# TopLevel.net
KiCad netlist of a schematic drawn in Altium Designer
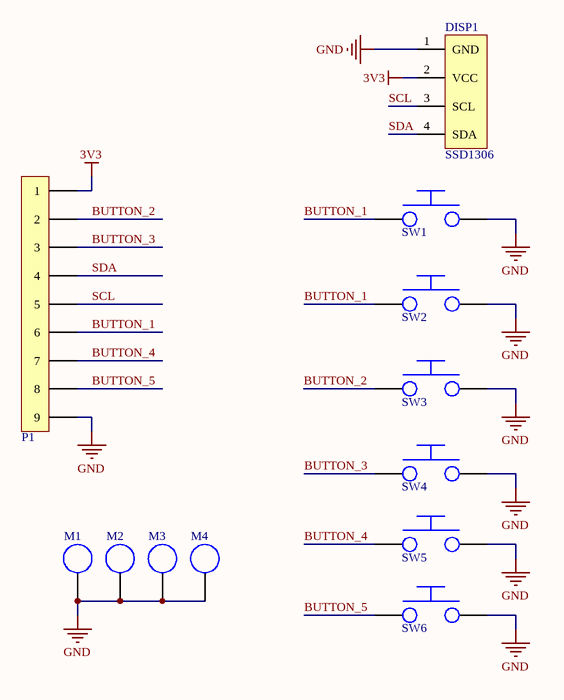
[diagram p0: TopLevel.SchDoc]

(export (version "E")
  (design (tool "Eeschema 10.0.6"))
  (components
    (comp (ref "DISP1")
      (value "SSD1306")
      (footprint "SSD1306_1.3")
      (description "SSD1306 128*64 1.3Inch I2C OLED Module")
      (libsource (lib "OneFader") (part "SSD1306_1.3"))
    )
    (comp (ref "M1")
      (value "M3 Flat Screw")
      (footprint "M3 Screw")
      (libsource (lib "OneFader") (part "M3 Flat Screw"))
    )
    (comp (ref "M2")
      (value "M3 Flat Screw")
      (footprint "M3 Screw")
      (libsource (lib "OneFader") (part "M3 Flat Screw"))
    )
    (comp (ref "M3")
      (value "M3 Flat Screw")
      (footprint "M3 Screw")
      (libsource (lib "OneFader") (part "M3 Flat Screw"))
    )
    (comp (ref "M4")
      (value "M3 Flat Screw")
      (footprint "M3 Screw")
      (libsource (lib "OneFader") (part "M3 Flat Screw"))
    )
    (comp (ref "P1") (value "9 Header") (footprint "9 Header") (libsource (lib "OneFader") (part "9 Header")))
    (comp (ref "SW1")
      (value "Momentary Button")
      (footprint "TD-19XA")
      (libsource (lib "OneFader") (part "Momentary Button"))
    )
    (comp (ref "SW2")
      (value "Momentary Button")
      (footprint "TS1127")
      (libsource (lib "OneFader") (part "Momentary Button"))
    )
    (comp (ref "SW3")
      (value "Momentary Button")
      (footprint "Tactile Button 6*6*5mm")
      (libsource (lib "OneFader") (part "Momentary Button"))
    )
    (comp (ref "SW4")
      (value "Momentary Button")
      (footprint "Tactile Button 6*6*5mm")
      (libsource (lib "OneFader") (part "Momentary Button"))
    )
    (comp (ref "SW5")
      (value "Momentary Button")
      (footprint "Tactile Button 6*6*5mm")
      (libsource (lib "OneFader") (part "Momentary Button"))
    )
    (comp (ref "SW6")
      (value "Momentary Button")
      (footprint "Tactile Button 6*6*5mm")
      (libsource (lib "OneFader") (part "Momentary Button"))
    )
  )
  (nets
    (net (code "1") (name "/BUTTON_1") (class "Default")
      (node (ref "P1") (pin "6") (pinfunction "6_6") (pintype "passive"))
      (node (ref "SW1") (pin "1") (pinfunction "1_1") (pintype "passive"))
      (node (ref "SW2") (pin "1") (pinfunction "1_1") (pintype "passive"))
    )
    (net (code "2") (name "/BUTTON_2") (class "Default")
      (node (ref "P1") (pin "2") (pinfunction "2_2") (pintype "passive"))
      (node (ref "SW3") (pin "1") (pinfunction "1_1") (pintype "passive"))
    )
    (net (code "3") (name "/BUTTON_3") (class "Default")
      (node (ref "P1") (pin "3") (pinfunction "3_3") (pintype "passive"))
      (node (ref "SW4") (pin "1") (pinfunction "1_1") (pintype "passive"))
    )
    (net (code "4") (name "/BUTTON_4") (class "Default")
      (node (ref "P1") (pin "7") (pinfunction "7_7") (pintype "passive"))
      (node (ref "SW5") (pin "1") (pinfunction "1_1") (pintype "passive"))
    )
    (net (code "5") (name "/BUTTON_5") (class "Default")
      (node (ref "P1") (pin "8") (pinfunction "8_8") (pintype "passive"))
      (node (ref "SW6") (pin "1") (pinfunction "1_1") (pintype "passive"))
    )
    (net (code "6") (name "/SCL") (class "Default")
      (node (ref "DISP1") (pin "3") (pinfunction "SCL_3") (pintype "passive"))
      (node (ref "P1") (pin "5") (pinfunction "5_5") (pintype "passive"))
    )
    (net (code "7") (name "/SDA") (class "Default")
      (node (ref "DISP1") (pin "4") (pinfunction "SDA_4") (pintype "passive"))
      (node (ref "P1") (pin "4") (pinfunction "4_4") (pintype "passive"))
    )
    (net (code "8") (name "3V3") (class "Default")
      (node (ref "DISP1") (pin "2") (pinfunction "VCC_2") (pintype "passive"))
      (node (ref "P1") (pin "1") (pinfunction "1_1") (pintype "passive"))
    )
    (net (code "9") (name "GND") (class "Default")
      (node (ref "DISP1") (pin "1") (pinfunction "GND_1") (pintype "passive"))
      (node (ref "M1") (pin "1") (pinfunction "1_1") (pintype "passive"))
      (node (ref "M2") (pin "1") (pinfunction "1_1") (pintype "passive"))
      (node (ref "M3") (pin "1") (pinfunction "1_1") (pintype "passive"))
      (node (ref "M4") (pin "1") (pinfunction "1_1") (pintype "passive"))
      (node (ref "P1") (pin "9") (pinfunction "9_9") (pintype "passive"))
      (node (ref "SW1") (pin "2") (pinfunction "2_2") (pintype "passive"))
      (node (ref "SW2") (pin "2") (pinfunction "2_2") (pintype "passive"))
      (node (ref "SW3") (pin "2") (pinfunction "2_2") (pintype "passive"))
      (node (ref "SW4") (pin "2") (pinfunction "2_2") (pintype "passive"))
      (node (ref "SW5") (pin "2") (pinfunction "2_2") (pintype "passive"))
      (node (ref "SW6") (pin "2") (pinfunction "2_2") (pintype "passive"))
    )
  )
)
